# 504_outin_chirimen.net
KiCad netlist of a schematic drawn in EAGLE
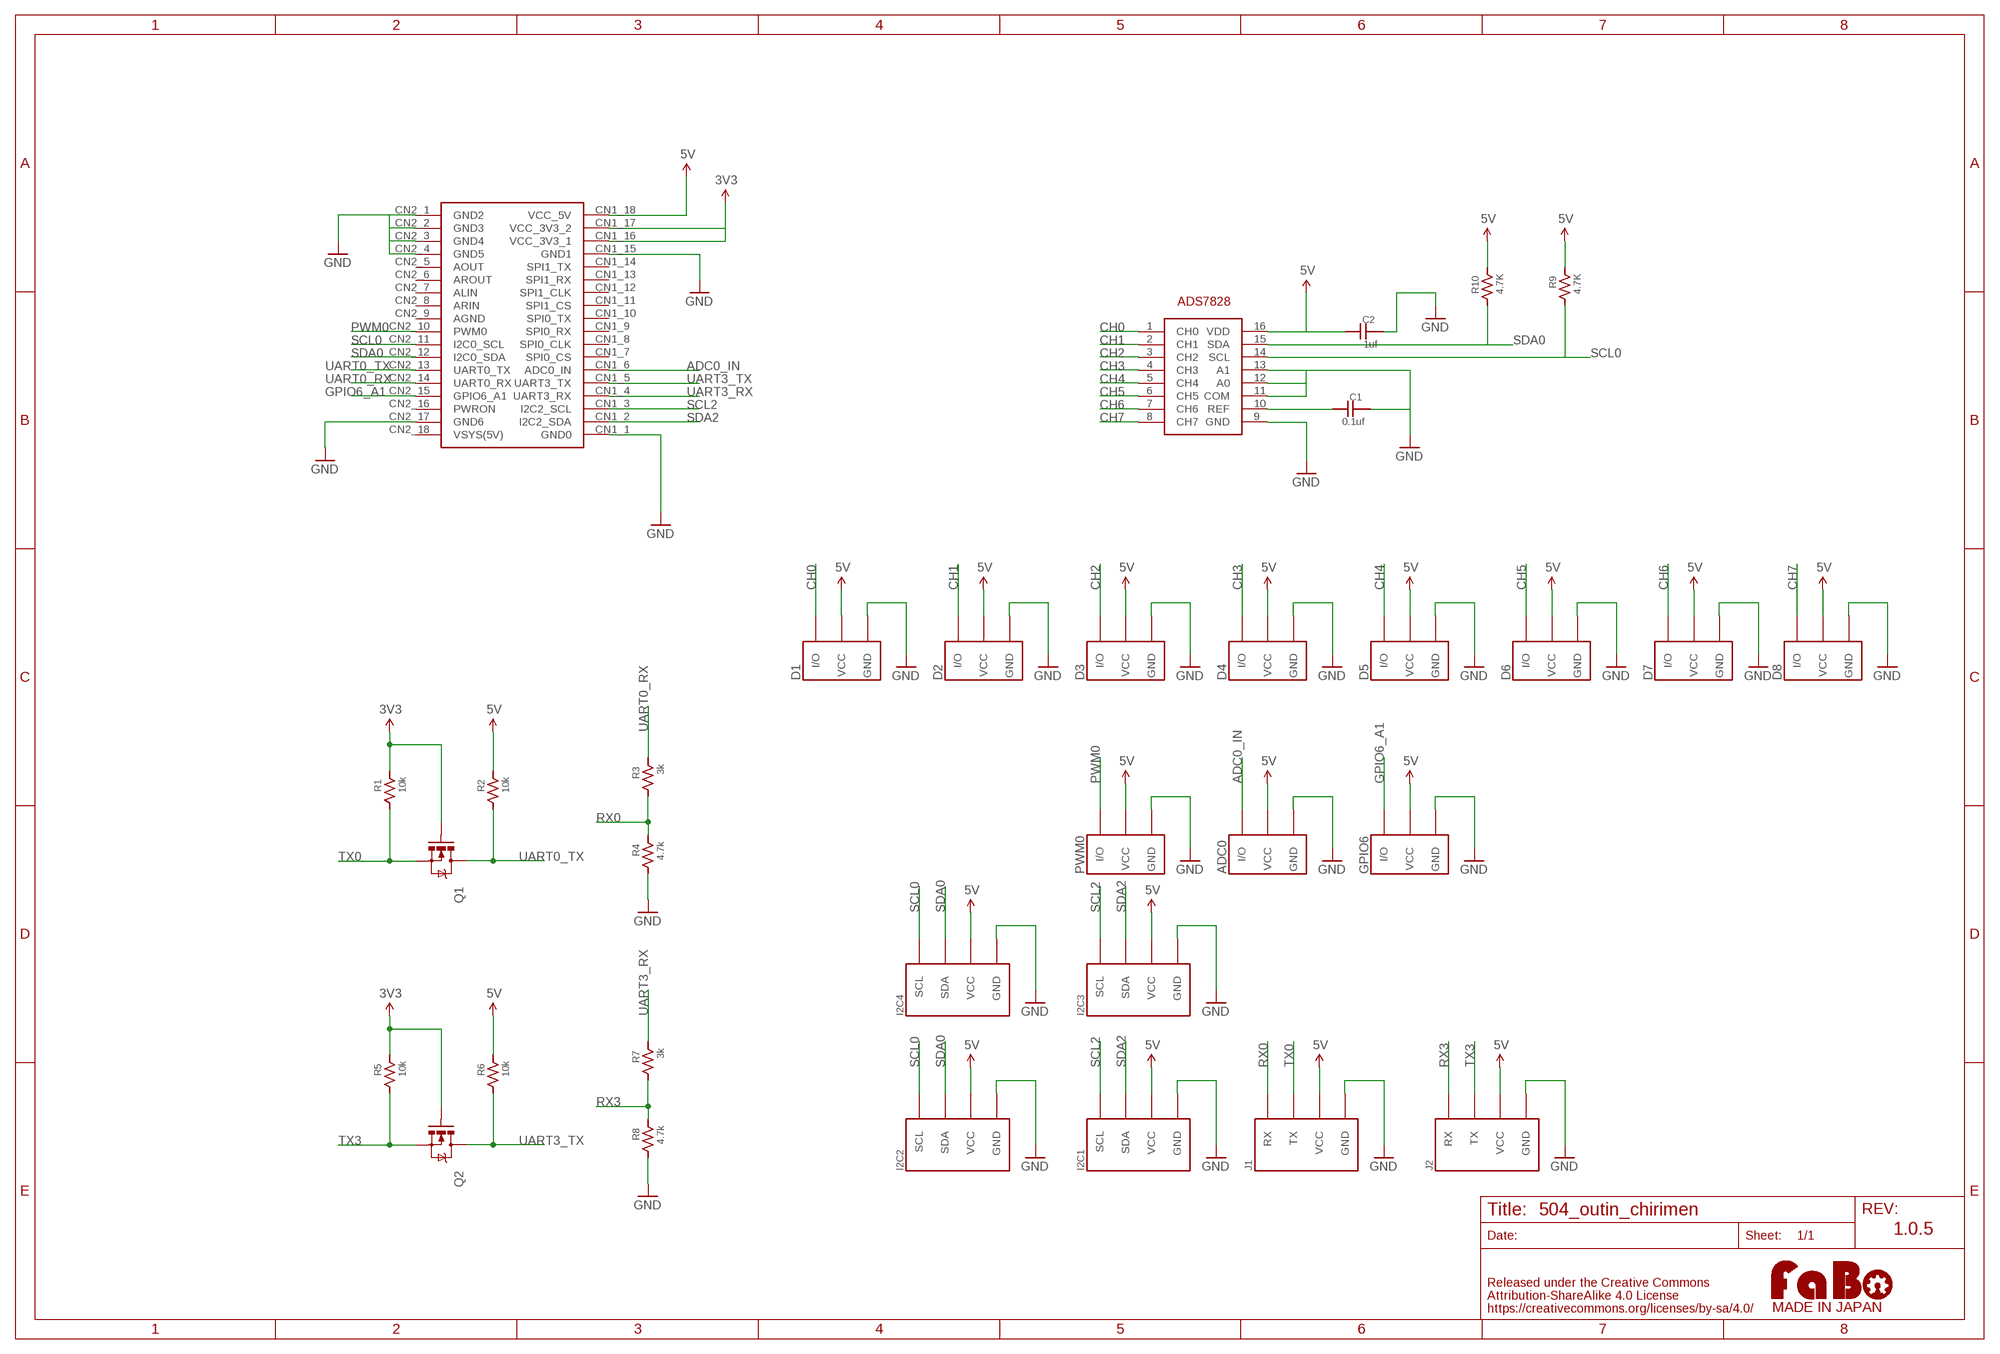
[diagram p0: schematic, sheet 1]

(export (version "E")
  (design (tool "Eeschema 10.0.6"))
  (components
    (comp (ref "ADC0")
      (value "FABO_BRICK_3PIN-HEADER")
      (footprint "eagle-import:FABO_BRICK_3PIN_HEADER")
      (libsource (lib "eagle-import") (part "FABO_BRICK_3PIN-HEADER"))
    )
    (comp (ref "C1")
      (value "0.1uf")
      (footprint "eagle-import:0402")
      (libsource (lib "eagle-import") (part "CAPACITOR0402"))
    )
    (comp (ref "C2")
      (value "1uf")
      (footprint "eagle-import:0402")
      (libsource (lib "eagle-import") (part "CAPACITOR0402"))
    )
    (comp (ref "D1")
      (value "FABO_BRICK_3PIN-B03B-PASK-1_SILK")
      (footprint "eagle-import:FABO_BRICK_3PIN_B03B-PASK-1_SILK")
      (libsource (lib "eagle-import") (part "FABO_BRICK_3PIN-B03B-PASK-1_SILK"))
    )
    (comp (ref "D2")
      (value "FABO_BRICK_3PIN-B03B-PASK-1_SILK")
      (footprint "eagle-import:FABO_BRICK_3PIN_B03B-PASK-1_SILK")
      (libsource (lib "eagle-import") (part "FABO_BRICK_3PIN-B03B-PASK-1_SILK"))
    )
    (comp (ref "D3")
      (value "FABO_BRICK_3PIN-B03B-PASK-1_SILK")
      (footprint "eagle-import:FABO_BRICK_3PIN_B03B-PASK-1_SILK")
      (libsource (lib "eagle-import") (part "FABO_BRICK_3PIN-B03B-PASK-1_SILK"))
    )
    (comp (ref "D4")
      (value "FABO_BRICK_3PIN-B03B-PASK-1_SILK")
      (footprint "eagle-import:FABO_BRICK_3PIN_B03B-PASK-1_SILK")
      (libsource (lib "eagle-import") (part "FABO_BRICK_3PIN-B03B-PASK-1_SILK"))
    )
    (comp (ref "D5")
      (value "FABO_BRICK_3PIN-B03B-PASK-1_SILK")
      (footprint "eagle-import:FABO_BRICK_3PIN_B03B-PASK-1_SILK")
      (libsource (lib "eagle-import") (part "FABO_BRICK_3PIN-B03B-PASK-1_SILK"))
    )
    (comp (ref "D6")
      (value "FABO_BRICK_3PIN-B03B-PASK-1_SILK")
      (footprint "eagle-import:FABO_BRICK_3PIN_B03B-PASK-1_SILK")
      (libsource (lib "eagle-import") (part "FABO_BRICK_3PIN-B03B-PASK-1_SILK"))
    )
    (comp (ref "D7")
      (value "FABO_BRICK_3PIN-B03B-PASK-1_SILK")
      (footprint "eagle-import:FABO_BRICK_3PIN_B03B-PASK-1_SILK")
      (libsource (lib "eagle-import") (part "FABO_BRICK_3PIN-B03B-PASK-1_SILK"))
    )
    (comp (ref "D8")
      (value "FABO_BRICK_3PIN-B03B-PASK-1_SILK")
      (footprint "eagle-import:FABO_BRICK_3PIN_B03B-PASK-1_SILK")
      (libsource (lib "eagle-import") (part "FABO_BRICK_3PIN-B03B-PASK-1_SILK"))
    )
    (comp (ref "GPIO6")
      (value "FABO_BRICK_3PIN-HEADER")
      (footprint "eagle-import:FABO_BRICK_3PIN_HEADER")
      (libsource (lib "eagle-import") (part "FABO_BRICK_3PIN-HEADER"))
    )
    (comp (ref "I2C1")
      (value "FABO_BRICK_I2C-B04B-PASK-1_SILK")
      (footprint "eagle-import:FABO_BRICK_I2C_B04B-PASK-1_SILK")
      (libsource (lib "eagle-import") (part "FABO_BRICK_I2C-B04B-PASK-1_SILK"))
    )
    (comp (ref "I2C2")
      (value "FABO_BRICK_I2C-B04B-PASK-1_SILK")
      (footprint "eagle-import:FABO_BRICK_I2C_B04B-PASK-1_SILK")
      (libsource (lib "eagle-import") (part "FABO_BRICK_I2C-B04B-PASK-1_SILK"))
    )
    (comp (ref "I2C3")
      (value "FABO_BRICK_I2C-B04B-PASK-1_SILK")
      (footprint "eagle-import:FABO_BRICK_I2C_B04B-PASK-1_SILK")
      (libsource (lib "eagle-import") (part "FABO_BRICK_I2C-B04B-PASK-1_SILK"))
    )
    (comp (ref "I2C4")
      (value "FABO_BRICK_I2C-B04B-PASK-1_SILK")
      (footprint "eagle-import:FABO_BRICK_I2C_B04B-PASK-1_SILK")
      (libsource (lib "eagle-import") (part "FABO_BRICK_I2C-B04B-PASK-1_SILK"))
    )
    (comp (ref "IC")
      (value "TI-ADS7828")
      (footprint "eagle-import:TI-ADS7828")
      (libsource (lib "eagle-import") (part "TI-ADS7828"))
    )
    (comp (ref "J1")
      (value "FABO_BRICK_SERIAL-S04B-PASK-2_SILK")
      (footprint "eagle-import:FABO_BRICK_SERIAL_S04B-PASK-2_SILK")
      (libsource (lib "eagle-import") (part "FABO_BRICK_SERIAL-S04B-PASK-2_SILK"))
    )
    (comp (ref "J2")
      (value "FABO_BRICK_SERIAL-S04B-PASK-2_SILK")
      (footprint "eagle-import:FABO_BRICK_SERIAL_S04B-PASK-2_SILK")
      (libsource (lib "eagle-import") (part "FABO_BRICK_SERIAL-S04B-PASK-2_SILK"))
    )
    (comp (ref "PWM0")
      (value "FABO_BRICK_3PIN-HEADER")
      (footprint "eagle-import:FABO_BRICK_3PIN_HEADER")
      (libsource (lib "eagle-import") (part "FABO_BRICK_3PIN-HEADER"))
    )
    (comp (ref "Q1")
      (value "MOSFET-N-BSS138")
      (footprint "eagle-import:SOT23-3")
      (libsource (lib "eagle-import") (part "MOSFET-N-BSS138"))
    )
    (comp (ref "Q2")
      (value "MOSFET-N-BSS138")
      (footprint "eagle-import:SOT23-3")
      (libsource (lib "eagle-import") (part "MOSFET-N-BSS138"))
    )
    (comp (ref "R1")
      (value "10k")
      (footprint "eagle-import:0402")
      (libsource (lib "eagle-import") (part "RESISTOR-0402"))
    )
    (comp (ref "R2")
      (value "10k")
      (footprint "eagle-import:0402")
      (libsource (lib "eagle-import") (part "RESISTOR-0402"))
    )
    (comp (ref "R3")
      (value "3k")
      (footprint "eagle-import:0402")
      (libsource (lib "eagle-import") (part "RESISTOR-0402"))
    )
    (comp (ref "R4")
      (value "4.7k")
      (footprint "eagle-import:0402")
      (libsource (lib "eagle-import") (part "RESISTOR-0402"))
    )
    (comp (ref "R5")
      (value "10k")
      (footprint "eagle-import:0402")
      (libsource (lib "eagle-import") (part "RESISTOR-0402"))
    )
    (comp (ref "R6")
      (value "10k")
      (footprint "eagle-import:0402")
      (libsource (lib "eagle-import") (part "RESISTOR-0402"))
    )
    (comp (ref "R7")
      (value "3k")
      (footprint "eagle-import:0402")
      (libsource (lib "eagle-import") (part "RESISTOR-0402"))
    )
    (comp (ref "R8")
      (value "4.7k")
      (footprint "eagle-import:0402")
      (libsource (lib "eagle-import") (part "RESISTOR-0402"))
    )
    (comp (ref "R9")
      (value "4.7K")
      (footprint "eagle-import:0402")
      (libsource (lib "eagle-import") (part "RESISTOR-0402"))
    )
    (comp (ref "R10")
      (value "4.7K")
      (footprint "eagle-import:0402")
      (libsource (lib "eagle-import") (part "RESISTOR-0402"))
    )
    (comp (ref "U$2")
      (value "FABO-CHIRIMEN")
      (footprint "eagle-import:FABO-CHIRIMEN")
      (libsource (lib "eagle-import") (part "FABO-CHIRIMEN"))
    )
    (comp (ref "U$10")
      (value "LOGO_FABO-M")
      (footprint "eagle-import:LOGO_FABO_MS")
      (libsource (lib "eagle-import") (part "LOGO_FABO-M"))
    )
  )
  (nets
    (net (code "1") (name "/ADC0_IN") (class "Default")
      (node (ref "ADC0") (pin "I/O") (pinfunction "I/O_I/O") (pintype "bidirectional"))
      (node (ref "U$2") (pin "CN1_6") (pinfunction "ADC0_IN_CN1_6") (pintype "bidirectional"))
    )
    (net (code "2") (name "/CH0") (class "Default")
      (node (ref "D1") (pin "I/O") (pinfunction "I/O_I/O") (pintype "bidirectional"))
      (node (ref "IC") (pin "1") (pinfunction "CH0_1") (pintype "bidirectional"))
    )
    (net (code "3") (name "/CH1") (class "Default")
      (node (ref "D2") (pin "I/O") (pinfunction "I/O_I/O") (pintype "bidirectional"))
      (node (ref "IC") (pin "2") (pinfunction "CH1_2") (pintype "bidirectional"))
    )
    (net (code "4") (name "/CH2") (class "Default")
      (node (ref "D3") (pin "I/O") (pinfunction "I/O_I/O") (pintype "bidirectional"))
      (node (ref "IC") (pin "3") (pinfunction "CH2_3") (pintype "bidirectional"))
    )
    (net (code "5") (name "/CH3") (class "Default")
      (node (ref "D4") (pin "I/O") (pinfunction "I/O_I/O") (pintype "bidirectional"))
      (node (ref "IC") (pin "4") (pinfunction "CH3_4") (pintype "bidirectional"))
    )
    (net (code "6") (name "/CH4") (class "Default")
      (node (ref "D5") (pin "I/O") (pinfunction "I/O_I/O") (pintype "bidirectional"))
      (node (ref "IC") (pin "5") (pinfunction "CH4_5") (pintype "bidirectional"))
    )
    (net (code "7") (name "/CH5") (class "Default")
      (node (ref "D6") (pin "I/O") (pinfunction "I/O_I/O") (pintype "bidirectional"))
      (node (ref "IC") (pin "6") (pinfunction "CH5_6") (pintype "bidirectional"))
    )
    (net (code "8") (name "/CH6") (class "Default")
      (node (ref "D7") (pin "I/O") (pinfunction "I/O_I/O") (pintype "bidirectional"))
      (node (ref "IC") (pin "7") (pinfunction "CH6_7") (pintype "bidirectional"))
    )
    (net (code "9") (name "/CH7") (class "Default")
      (node (ref "D8") (pin "I/O") (pinfunction "I/O_I/O") (pintype "bidirectional"))
      (node (ref "IC") (pin "8") (pinfunction "CH7_8") (pintype "bidirectional"))
    )
    (net (code "10") (name "/GPIO6_A1") (class "Default")
      (node (ref "GPIO6") (pin "I/O") (pinfunction "I/O_I/O") (pintype "bidirectional"))
      (node (ref "U$2") (pin "CN2_15") (pinfunction "GPIO6_A1_CN2_15") (pintype "bidirectional"))
    )
    (net (code "11") (name "/PWM0") (class "Default")
      (node (ref "PWM0") (pin "I/O") (pinfunction "I/O_I/O") (pintype "bidirectional"))
      (node (ref "U$2") (pin "CN2_10") (pinfunction "PWM0_CN2_10") (pintype "bidirectional"))
    )
    (net (code "12") (name "/RX0") (class "Default")
      (node (ref "J1") (pin "RX") (pinfunction "RX_RX") (pintype "bidirectional"))
      (node (ref "R3") (pin "P$1") (pinfunction "1_P$1") (pintype "bidirectional"))
      (node (ref "R4") (pin "P$2") (pinfunction "2_P$2") (pintype "bidirectional"))
    )
    (net (code "13") (name "/RX3") (class "Default")
      (node (ref "J2") (pin "RX") (pinfunction "RX_RX") (pintype "bidirectional"))
      (node (ref "R7") (pin "P$1") (pinfunction "1_P$1") (pintype "bidirectional"))
      (node (ref "R8") (pin "P$2") (pinfunction "2_P$2") (pintype "bidirectional"))
    )
    (net (code "14") (name "/SCL0") (class "Default")
      (node (ref "I2C2") (pin "SCL") (pinfunction "SCL_SCL") (pintype "bidirectional"))
      (node (ref "I2C4") (pin "SCL") (pinfunction "SCL_SCL") (pintype "bidirectional"))
      (node (ref "IC") (pin "14") (pinfunction "SCL_14") (pintype "bidirectional"))
      (node (ref "R9") (pin "P$1") (pinfunction "1_P$1") (pintype "bidirectional"))
      (node (ref "U$2") (pin "CN2_11") (pinfunction "I2C0_SCL_CN2_11") (pintype "bidirectional"))
    )
    (net (code "15") (name "/SCL2") (class "Default")
      (node (ref "I2C1") (pin "SCL") (pinfunction "SCL_SCL") (pintype "bidirectional"))
      (node (ref "I2C3") (pin "SCL") (pinfunction "SCL_SCL") (pintype "bidirectional"))
      (node (ref "U$2") (pin "CN1_3") (pinfunction "I2C2_SCL_CN1_3") (pintype "bidirectional"))
    )
    (net (code "16") (name "/SDA0") (class "Default")
      (node (ref "I2C2") (pin "SDA") (pinfunction "SDA_SDA") (pintype "bidirectional"))
      (node (ref "I2C4") (pin "SDA") (pinfunction "SDA_SDA") (pintype "bidirectional"))
      (node (ref "IC") (pin "15") (pinfunction "SDA_15") (pintype "bidirectional"))
      (node (ref "R10") (pin "P$1") (pinfunction "1_P$1") (pintype "bidirectional"))
      (node (ref "U$2") (pin "CN2_12") (pinfunction "I2C0_SDA_CN2_12") (pintype "bidirectional"))
    )
    (net (code "17") (name "/SDA2") (class "Default")
      (node (ref "I2C1") (pin "SDA") (pinfunction "SDA_SDA") (pintype "bidirectional"))
      (node (ref "I2C3") (pin "SDA") (pinfunction "SDA_SDA") (pintype "bidirectional"))
      (node (ref "U$2") (pin "CN1_2") (pinfunction "I2C2_SDA_CN1_2") (pintype "bidirectional"))
    )
    (net (code "18") (name "/TX0") (class "Default")
      (node (ref "J1") (pin "TX") (pinfunction "TX_TX") (pintype "bidirectional"))
      (node (ref "Q1") (pin "2") (pinfunction "S_2") (pintype "passive"))
      (node (ref "R1") (pin "P$1") (pinfunction "1_P$1") (pintype "bidirectional"))
    )
    (net (code "19") (name "/TX3") (class "Default")
      (node (ref "J2") (pin "TX") (pinfunction "TX_TX") (pintype "bidirectional"))
      (node (ref "Q2") (pin "2") (pinfunction "S_2") (pintype "passive"))
      (node (ref "R5") (pin "P$1") (pinfunction "1_P$1") (pintype "bidirectional"))
    )
    (net (code "20") (name "/UART0_RX") (class "Default")
      (node (ref "R3") (pin "P$2") (pinfunction "2_P$2") (pintype "bidirectional"))
      (node (ref "U$2") (pin "CN2_14") (pinfunction "UART0_RX_CN2_14") (pintype "bidirectional"))
    )
    (net (code "21") (name "/UART0_TX") (class "Default")
      (node (ref "Q1") (pin "3") (pinfunction "D_3") (pintype "passive"))
      (node (ref "R2") (pin "P$1") (pinfunction "1_P$1") (pintype "bidirectional"))
      (node (ref "U$2") (pin "CN2_13") (pinfunction "UART0_TX_CN2_13") (pintype "bidirectional"))
    )
    (net (code "22") (name "/UART3_RX") (class "Default")
      (node (ref "R7") (pin "P$2") (pinfunction "2_P$2") (pintype "bidirectional"))
      (node (ref "U$2") (pin "CN1_4") (pinfunction "UART3_RX_CN1_4") (pintype "bidirectional"))
    )
    (net (code "23") (name "/UART3_TX") (class "Default")
      (node (ref "Q2") (pin "3") (pinfunction "D_3") (pintype "passive"))
      (node (ref "R6") (pin "P$1") (pinfunction "1_P$1") (pintype "bidirectional"))
      (node (ref "U$2") (pin "CN1_5") (pinfunction "UART3_TX_CN1_5") (pintype "bidirectional"))
    )
    (net (code "24") (name "3V3") (class "Default")
      (node (ref "Q1") (pin "1") (pinfunction "G_1") (pintype "passive"))
      (node (ref "Q2") (pin "1") (pinfunction "G_1") (pintype "passive"))
      (node (ref "R1") (pin "P$2") (pinfunction "2_P$2") (pintype "bidirectional"))
      (node (ref "R5") (pin "P$2") (pinfunction "2_P$2") (pintype "bidirectional"))
      (node (ref "U$2") (pin "CN1_16") (pinfunction "VCC_3V3_1_CN1_16") (pintype "bidirectional"))
      (node (ref "U$2") (pin "CN1_17") (pinfunction "VCC_3V3_2_CN1_17") (pintype "bidirectional"))
    )
    (net (code "25") (name "5V") (class "Default")
      (node (ref "ADC0") (pin "VCC") (pinfunction "VCC_VCC") (pintype "bidirectional"))
      (node (ref "C2") (pin "P$1") (pinfunction "1_P$1") (pintype "passive"))
      (node (ref "D1") (pin "VCC") (pinfunction "VCC_VCC") (pintype "bidirectional"))
      (node (ref "D2") (pin "VCC") (pinfunction "VCC_VCC") (pintype "bidirectional"))
      (node (ref "D3") (pin "VCC") (pinfunction "VCC_VCC") (pintype "bidirectional"))
      (node (ref "D4") (pin "VCC") (pinfunction "VCC_VCC") (pintype "bidirectional"))
      (node (ref "D5") (pin "VCC") (pinfunction "VCC_VCC") (pintype "bidirectional"))
      (node (ref "D6") (pin "VCC") (pinfunction "VCC_VCC") (pintype "bidirectional"))
      (node (ref "D7") (pin "VCC") (pinfunction "VCC_VCC") (pintype "bidirectional"))
      (node (ref "D8") (pin "VCC") (pinfunction "VCC_VCC") (pintype "bidirectional"))
      (node (ref "GPIO6") (pin "VCC") (pinfunction "VCC_VCC") (pintype "bidirectional"))
      (node (ref "I2C1") (pin "VCC") (pinfunction "VCC_VCC") (pintype "bidirectional"))
      (node (ref "I2C2") (pin "VCC") (pinfunction "VCC_VCC") (pintype "bidirectional"))
      (node (ref "I2C3") (pin "VCC") (pinfunction "VCC_VCC") (pintype "bidirectional"))
      (node (ref "I2C4") (pin "VCC") (pinfunction "VCC_VCC") (pintype "bidirectional"))
      (node (ref "IC") (pin "16") (pinfunction "VDD_16") (pintype "bidirectional"))
      (node (ref "J1") (pin "VCC") (pinfunction "VCC_VCC") (pintype "bidirectional"))
      (node (ref "J2") (pin "VCC") (pinfunction "VCC_VCC") (pintype "bidirectional"))
      (node (ref "PWM0") (pin "VCC") (pinfunction "VCC_VCC") (pintype "bidirectional"))
      (node (ref "R10") (pin "P$2") (pinfunction "2_P$2") (pintype "bidirectional"))
      (node (ref "R2") (pin "P$2") (pinfunction "2_P$2") (pintype "bidirectional"))
      (node (ref "R6") (pin "P$2") (pinfunction "2_P$2") (pintype "bidirectional"))
      (node (ref "R9") (pin "P$2") (pinfunction "2_P$2") (pintype "bidirectional"))
      (node (ref "U$2") (pin "CN1_18") (pinfunction "VCC_5V_CN1_18") (pintype "bidirectional"))
    )
    (net (code "26") (name "GND") (class "Default")
      (node (ref "ADC0") (pin "GND") (pinfunction "GND_GND") (pintype "bidirectional"))
      (node (ref "C1") (pin "P$2") (pinfunction "2_P$2") (pintype "passive"))
      (node (ref "C2") (pin "P$2") (pinfunction "2_P$2") (pintype "passive"))
      (node (ref "D1") (pin "GND") (pinfunction "GND_GND") (pintype "bidirectional"))
      (node (ref "D2") (pin "GND") (pinfunction "GND_GND") (pintype "bidirectional"))
      (node (ref "D3") (pin "GND") (pinfunction "GND_GND") (pintype "bidirectional"))
      (node (ref "D4") (pin "GND") (pinfunction "GND_GND") (pintype "bidirectional"))
      (node (ref "D5") (pin "GND") (pinfunction "GND_GND") (pintype "bidirectional"))
      (node (ref "D6") (pin "GND") (pinfunction "GND_GND") (pintype "bidirectional"))
      (node (ref "D7") (pin "GND") (pinfunction "GND_GND") (pintype "bidirectional"))
      (node (ref "D8") (pin "GND") (pinfunction "GND_GND") (pintype "bidirectional"))
      (node (ref "GPIO6") (pin "GND") (pinfunction "GND_GND") (pintype "bidirectional"))
      (node (ref "I2C1") (pin "GND") (pinfunction "GND_GND") (pintype "bidirectional"))
      (node (ref "I2C2") (pin "GND") (pinfunction "GND_GND") (pintype "bidirectional"))
      (node (ref "I2C3") (pin "GND") (pinfunction "GND_GND") (pintype "bidirectional"))
      (node (ref "I2C4") (pin "GND") (pinfunction "GND_GND") (pintype "bidirectional"))
      (node (ref "IC") (pin "11") (pinfunction "COM_11") (pintype "bidirectional"))
      (node (ref "IC") (pin "12") (pinfunction "A0_12") (pintype "bidirectional"))
      (node (ref "IC") (pin "13") (pinfunction "A1_13") (pintype "bidirectional"))
      (node (ref "IC") (pin "9") (pinfunction "GND_9") (pintype "bidirectional"))
      (node (ref "J1") (pin "GND") (pinfunction "GND_GND") (pintype "bidirectional"))
      (node (ref "J2") (pin "GND") (pinfunction "GND_GND") (pintype "bidirectional"))
      (node (ref "PWM0") (pin "GND") (pinfunction "GND_GND") (pintype "bidirectional"))
      (node (ref "R4") (pin "P$1") (pinfunction "1_P$1") (pintype "bidirectional"))
      (node (ref "R8") (pin "P$1") (pinfunction "1_P$1") (pintype "bidirectional"))
      (node (ref "U$2") (pin "CN1_1") (pinfunction "GND0_CN1_1") (pintype "bidirectional"))
      (node (ref "U$2") (pin "CN1_15") (pinfunction "GND1_CN1_15") (pintype "bidirectional"))
      (node (ref "U$2") (pin "CN2_1") (pinfunction "GND2_CN2_1") (pintype "bidirectional"))
      (node (ref "U$2") (pin "CN2_17") (pinfunction "GND6_CN2_17") (pintype "bidirectional"))
      (node (ref "U$2") (pin "CN2_2") (pinfunction "GND3_CN2_2") (pintype "bidirectional"))
      (node (ref "U$2") (pin "CN2_3") (pinfunction "GND4_CN2_3") (pintype "bidirectional"))
      (node (ref "U$2") (pin "CN2_4") (pinfunction "GND5_CN2_4") (pintype "bidirectional"))
    )
    (net (code "27") (name "Net-(C1-1)") (class "Default")
      (node (ref "C1") (pin "P$1") (pinfunction "1_P$1") (pintype "passive"))
      (node (ref "IC") (pin "10") (pinfunction "REF_10") (pintype "bidirectional"))
    )
    (net (code "28") (name "unconnected-(U$2-AGND-PadCN2_9)") (class "Default")
      (node (ref "U$2") (pin "CN2_9") (pinfunction "AGND_CN2_9") (pintype "bidirectional"))
    )
    (net (code "29") (name "unconnected-(U$2-ALIN-PadCN2_7)") (class "Default")
      (node (ref "U$2") (pin "CN2_7") (pinfunction "ALIN_CN2_7") (pintype "bidirectional"))
    )
    (net (code "30") (name "unconnected-(U$2-AOUT-PadCN2_5)") (class "Default")
      (node (ref "U$2") (pin "CN2_5") (pinfunction "AOUT_CN2_5") (pintype "bidirectional"))
    )
    (net (code "31") (name "unconnected-(U$2-ARIN-PadCN2_8)") (class "Default")
      (node (ref "U$2") (pin "CN2_8") (pinfunction "ARIN_CN2_8") (pintype "bidirectional"))
    )
    (net (code "32") (name "unconnected-(U$2-AROUT-PadCN2_6)") (class "Default")
      (node (ref "U$2") (pin "CN2_6") (pinfunction "AROUT_CN2_6") (pintype "bidirectional"))
    )
    (net (code "33") (name "unconnected-(U$2-PWRON-PadCN2_16)") (class "Default")
      (node (ref "U$2") (pin "CN2_16") (pinfunction "PWRON_CN2_16") (pintype "bidirectional"))
    )
    (net (code "34") (name "unconnected-(U$2-SPI0_CLK-PadCN1_8)") (class "Default")
      (node (ref "U$2") (pin "CN1_8") (pinfunction "SPI0_CLK_CN1_8") (pintype "bidirectional"))
    )
    (net (code "35") (name "unconnected-(U$2-SPI0_CS-PadCN1_7)") (class "Default")
      (node (ref "U$2") (pin "CN1_7") (pinfunction "SPI0_CS_CN1_7") (pintype "bidirectional"))
    )
    (net (code "36") (name "unconnected-(U$2-SPI0_RX-PadCN1_9)") (class "Default")
      (node (ref "U$2") (pin "CN1_9") (pinfunction "SPI0_RX_CN1_9") (pintype "bidirectional"))
    )
    (net (code "37") (name "unconnected-(U$2-SPI0_TX-PadCN1_10)") (class "Default")
      (node (ref "U$2") (pin "CN1_10") (pinfunction "SPI0_TX_CN1_10") (pintype "bidirectional"))
    )
    (net (code "38") (name "unconnected-(U$2-SPI1_CLK-PadCN1_12)") (class "Default")
      (node (ref "U$2") (pin "CN1_12") (pinfunction "SPI1_CLK_CN1_12") (pintype "bidirectional"))
    )
    (net (code "39") (name "unconnected-(U$2-SPI1_CS-PadCN1_11)") (class "Default")
      (node (ref "U$2") (pin "CN1_11") (pinfunction "SPI1_CS_CN1_11") (pintype "bidirectional"))
    )
    (net (code "40") (name "unconnected-(U$2-SPI1_RX-PadCN1_13)") (class "Default")
      (node (ref "U$2") (pin "CN1_13") (pinfunction "SPI1_RX_CN1_13") (pintype "bidirectional"))
    )
    (net (code "41") (name "unconnected-(U$2-SPI1_TX-PadCN1_14)") (class "Default")
      (node (ref "U$2") (pin "CN1_14") (pinfunction "SPI1_TX_CN1_14") (pintype "bidirectional"))
    )
    (net (code "42") (name "unconnected-(U$2-VSYS(5V)-PadCN2_18)") (class "Default")
      (node (ref "U$2") (pin "CN2_18") (pinfunction "VSYS(5V)_CN2_18") (pintype "bidirectional"))
    )
  )
)
